# design.net
KiCad netlist of a schematic drawn in EasyEDA Pro
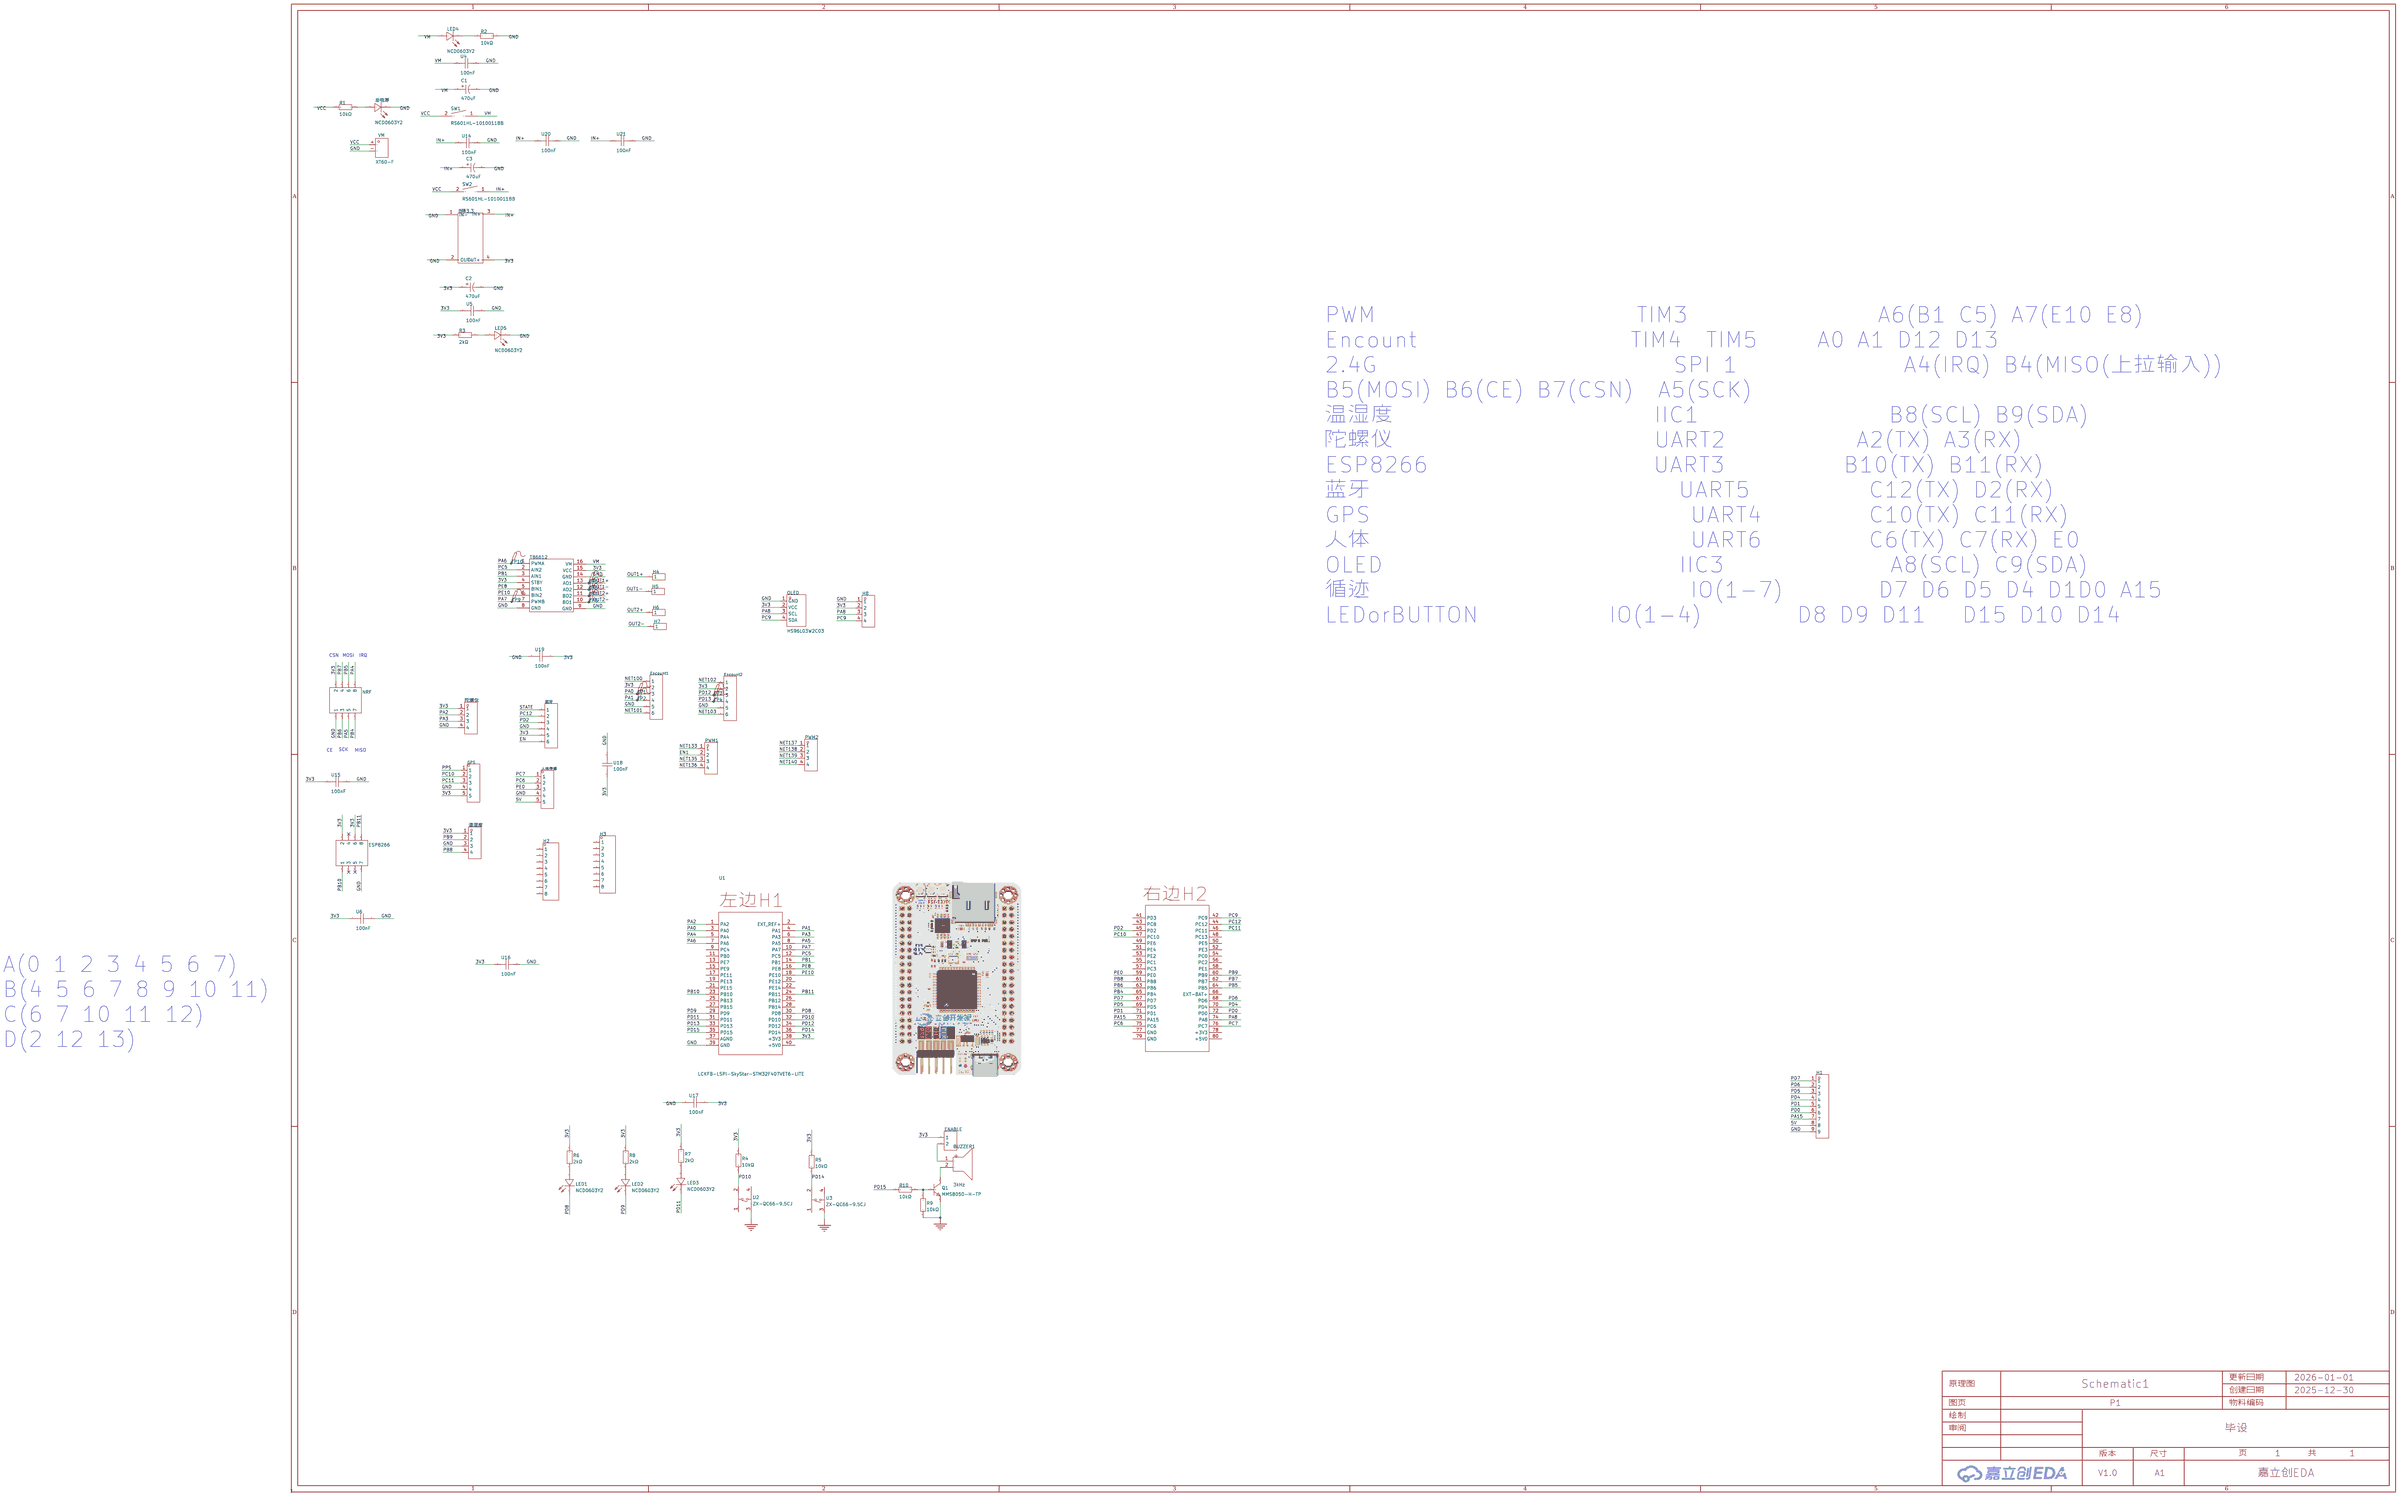
[diagram p0: schematic sheet]

(export (version "E")
  (design (tool "Eeschema 10.0.6"))
  (components
    (comp (ref "8降3.3")
      (value "~")
      (footprint "easyedapro:DCDC")
      (libsource (lib "easyedapro") (part "DCDC"))
    )
    (comp (ref "BUZZER1")
      (value "3kHz")
      (footprint "easyedapro:BUZ-TH_BD9.0-P5.00-D0.6-FD")
      (description "驱动方式:有源(内含驱动线路);构造类型:电磁式;频率:3kHz;声压(SPL):85dB;")
      (fields (field (name "Manufacturer Part") "HNB09A03") (field (name "Manufacturer") "华能"))
      (libsource (lib "easyedapro") (part "HNB09A03"))
    )
    (comp (ref "C1")
      (value "470uF")
      (footprint "easyedapro:CAP-TH_BD8.0-P3.50-D0.6-FD_1")
      (description "容值:470uF;精度:±20%;额定电压:25V;纹波电流:905mA@100kHz;等效串联电阻(ESR):69mΩ@100kHz;")
      (fields
        (field (name "Manufacturer Part") "CD2884771EM0812VFL")
        (field (name "Manufacturer") "HRK(鸿瑞凯电子)")
      )
      (libsource (lib "easyedapro") (part "CD2884771EM0812VFL"))
    )
    (comp (ref "C2")
      (value "470uF")
      (footprint "easyedapro:CAP-TH_BD8.0-P3.50-D0.6-FD_1")
      (description "容值:470uF;精度:±20%;额定电压:25V;纹波电流:905mA@100kHz;等效串联电阻(ESR):69mΩ@100kHz;")
      (fields
        (field (name "Manufacturer Part") "CD2884771EM0812VFL")
        (field (name "Manufacturer") "HRK(鸿瑞凯电子)")
      )
      (libsource (lib "easyedapro") (part "CD2884771EM0812VFL"))
    )
    (comp (ref "C3")
      (value "470uF")
      (footprint "easyedapro:CAP-TH_BD8.0-P3.50-D0.6-FD_1")
      (description "容值:470uF;精度:±20%;额定电压:25V;纹波电流:905mA@100kHz;等效串联电阻(ESR):69mΩ@100kHz;")
      (fields
        (field (name "Manufacturer Part") "CD2884771EM0812VFL")
        (field (name "Manufacturer") "HRK(鸿瑞凯电子)")
      )
      (libsource (lib "easyedapro") (part "CD2884771EM0812VFL"))
    )
    (comp (ref "ENABLE")
      (value "~")
      (footprint "easyedapro:HDR-TH_2P-P2.54-V-F")
      (libsource (lib "easyedapro") (part "Header-Female-2.54_1x2"))
    )
    (comp (ref "Encount1")
      (value "~")
      (footprint "easyedapro:HDR-TH_6P-P2.54-V-M-1")
      (libsource (lib "easyedapro") (part "Header-Male-2.54_1x6"))
    )
    (comp (ref "Encount2")
      (value "~")
      (footprint "easyedapro:HDR-TH_6P-P2.54-V-M-1")
      (libsource (lib "easyedapro") (part "Header-Male-2.54_1x6"))
    )
    (comp (ref "ESP8266")
      (value "~")
      (footprint "easyedapro:HDR-TH_8P-P2.54-V-F-R2-C4-S2.54-1")
      (libsource (lib "easyedapro") (part "HDR-F-2.54_2x4"))
    )
    (comp (ref "GPS")
      (value "~")
      (footprint "easyedapro:HDR-TH_5P-P2.54-V-M")
      (libsource (lib "easyedapro") (part "MTP125-1105S1"))
    )
    (comp (ref "H1")
      (value "~")
      (footprint "easyedapro:HDR-TH_9P-P2.54-V-M")
      (libsource (lib "easyedapro") (part "PZ254V-11-09P"))
    )
    (comp (ref "H2")
      (value "~")
      (footprint "easyedapro:HDR-TH_8P-P2.54-V-M")
      (libsource (lib "easyedapro") (part "Header-Male-2.54_1x8"))
    )
    (comp (ref "H3")
      (value "~")
      (footprint "easyedapro:HDR-TH_8P-P2.54-V-M")
      (libsource (lib "easyedapro") (part "Header-Male-2.54_1x8"))
    )
    (comp (ref "H4")
      (value "~")
      (footprint "easyedapro:HDR-TH_1P-V-M_XKB_X4611WV-01I-C28D40")
      (libsource (lib "easyedapro") (part "HDR_1x1"))
    )
    (comp (ref "H5")
      (value "~")
      (footprint "easyedapro:HDR-TH_1P-V-M_XKB_X4611WV-01I-C28D40")
      (libsource (lib "easyedapro") (part "HDR_1x1"))
    )
    (comp (ref "H6")
      (value "~")
      (footprint "easyedapro:HDR-TH_1P-V-M_XKB_X4611WV-01I-C28D40")
      (libsource (lib "easyedapro") (part "HDR_1x1"))
    )
    (comp (ref "H7")
      (value "~")
      (footprint "easyedapro:HDR-TH_1P-V-M_XKB_X4611WV-01I-C28D40")
      (libsource (lib "easyedapro") (part "HDR_1x1"))
    )
    (comp (ref "H8")
      (value "~")
      (footprint "easyedapro:HDR-TH_4P-P2.54-V-M")
      (libsource (lib "easyedapro") (part "PZ254V-11-04P"))
    )
    (comp (ref "LED1")
      (value "NCD0603Y2")
      (footprint "easyedapro:LED0603-RD")
      (fields (field (name "Manufacturer") "国星光电"))
      (libsource (lib "easyedapro") (part "FC-1608YXK-585F08"))
    )
    (comp (ref "LED2")
      (value "NCD0603Y2")
      (footprint "easyedapro:LED0603-RD")
      (fields (field (name "Manufacturer") "国星光电"))
      (libsource (lib "easyedapro") (part "FC-1608YXK-585F08"))
    )
    (comp (ref "LED3")
      (value "NCD0603Y2")
      (footprint "easyedapro:LED0603-RD")
      (fields (field (name "Manufacturer") "国星光电"))
      (libsource (lib "easyedapro") (part "FC-1608YXK-585F08"))
    )
    (comp (ref "LED4")
      (value "NCD0603Y2")
      (footprint "easyedapro:LED0603-RD")
      (fields (field (name "Manufacturer") "国星光电"))
      (libsource (lib "easyedapro") (part "FC-1608YXK-585F08"))
    )
    (comp (ref "LED5")
      (value "NCD0603Y2")
      (footprint "easyedapro:LED0603-RD")
      (fields (field (name "Manufacturer") "国星光电"))
      (libsource (lib "easyedapro") (part "FC-1608YXK-585F08"))
    )
    (comp (ref "NRF")
      (value "~")
      (footprint "easyedapro:HDR-TH_8P-P2.54-V-F-R2-C4-S2.54-1")
      (libsource (lib "easyedapro") (part "HDR-F-2.54_2x4"))
    )
    (comp (ref "OLED")
      (value "HS96L03W2C03")
      (footprint "easyedapro:OLED-TH_L27.8-W27.2-P2.54_C9900033791")
      (description "主控芯片:SSD1315;接口类型:I2C;尺寸(inch):0.96;像素分辨率:128x64;")
      (fields (field (name "Manufacturer") "HS(汉昇)"))
      (libsource (lib "easyedapro") (part "HS96L03W2C03"))
    )
    (comp (ref "PWM1")
      (value "~")
      (footprint "easyedapro:HDR-TH_4P-P2.54-V-M")
      (libsource (lib "easyedapro") (part "PZ254V-11-04P"))
    )
    (comp (ref "PWM2")
      (value "~")
      (footprint "easyedapro:HDR-TH_4P-P2.54-V-M")
      (libsource (lib "easyedapro") (part "PZ254V-11-04P"))
    )
    (comp (ref "Q1")
      (value "MMS8050-H-TP")
      (footprint "easyedapro:SOT-23-3_L2.9-W1.3-P1.90-LS2.4-BR")
      (description "晶体管类型:NPN;集电极电流(Ic):500mA;集射极击穿电压(Vceo):25V;耗散功率(Pd):300mW;直流电流增益(hFE):120@50mA,1V;")
      (fields (field (name "Manufacturer") "MCC(美微科)"))
      (libsource (lib "easyedapro") (part "MMS8050-H-TP"))
    )
    (comp (ref "R1")
      (value "10kΩ")
      (footprint "easyedapro:R0603")
      (description "电阻类型:厚膜电阻;阻值:4.7kΩ;精度:±1%;功率:100mW;工作电压:75V;温度系数:±100ppm/°C;")
      (fields
        (field (name "Manufacturer Part") "0603WAF4701T5E")
        (field (name "Manufacturer") "UNI-ROYAL(厚声)")
      )
      (libsource (lib "easyedapro") (part "0603WAF4701T5E"))
    )
    (comp (ref "R2")
      (value "10kΩ")
      (footprint "easyedapro:R0603")
      (description "电阻类型:厚膜电阻;阻值:4.7kΩ;精度:±1%;功率:100mW;工作电压:75V;温度系数:±100ppm/°C;")
      (fields
        (field (name "Manufacturer Part") "0603WAF4701T5E")
        (field (name "Manufacturer") "UNI-ROYAL(厚声)")
      )
      (libsource (lib "easyedapro") (part "0603WAF4701T5E"))
    )
    (comp (ref "R3")
      (value "2kΩ")
      (footprint "easyedapro:R0603")
      (description "电阻类型:厚膜电阻;阻值:4.7kΩ;精度:±1%;功率:100mW;工作电压:75V;温度系数:±100ppm/°C;")
      (fields
        (field (name "Manufacturer Part") "0603WAF4701T5E")
        (field (name "Manufacturer") "UNI-ROYAL(厚声)")
      )
      (libsource (lib "easyedapro") (part "0603WAF4701T5E"))
    )
    (comp (ref "R4")
      (value "10kΩ")
      (footprint "easyedapro:R0603")
      (description "电阻类型:厚膜电阻;阻值:4.7kΩ;精度:±1%;功率:100mW;工作电压:75V;温度系数:±100ppm/°C;")
      (fields
        (field (name "Manufacturer Part") "0603WAF4701T5E")
        (field (name "Manufacturer") "UNI-ROYAL(厚声)")
      )
      (libsource (lib "easyedapro") (part "0603WAF4701T5E"))
    )
    (comp (ref "R5")
      (value "10kΩ")
      (footprint "easyedapro:R0603")
      (description "电阻类型:厚膜电阻;阻值:4.7kΩ;精度:±1%;功率:100mW;工作电压:75V;温度系数:±100ppm/°C;")
      (fields
        (field (name "Manufacturer Part") "0603WAF4701T5E")
        (field (name "Manufacturer") "UNI-ROYAL(厚声)")
      )
      (libsource (lib "easyedapro") (part "0603WAF4701T5E"))
    )
    (comp (ref "R6")
      (value "2kΩ")
      (footprint "easyedapro:R0603")
      (description "电阻类型:厚膜电阻;阻值:4.7kΩ;精度:±1%;功率:100mW;工作电压:75V;温度系数:±100ppm/°C;")
      (fields
        (field (name "Manufacturer Part") "0603WAF4701T5E")
        (field (name "Manufacturer") "UNI-ROYAL(厚声)")
      )
      (libsource (lib "easyedapro") (part "0603WAF4701T5E"))
    )
    (comp (ref "R7")
      (value "2kΩ")
      (footprint "easyedapro:R0603")
      (description "电阻类型:厚膜电阻;阻值:4.7kΩ;精度:±1%;功率:100mW;工作电压:75V;温度系数:±100ppm/°C;")
      (fields
        (field (name "Manufacturer Part") "0603WAF4701T5E")
        (field (name "Manufacturer") "UNI-ROYAL(厚声)")
      )
      (libsource (lib "easyedapro") (part "0603WAF4701T5E"))
    )
    (comp (ref "R8")
      (value "2kΩ")
      (footprint "easyedapro:R0603")
      (description "电阻类型:厚膜电阻;阻值:4.7kΩ;精度:±1%;功率:100mW;工作电压:75V;温度系数:±100ppm/°C;")
      (fields
        (field (name "Manufacturer Part") "0603WAF4701T5E")
        (field (name "Manufacturer") "UNI-ROYAL(厚声)")
      )
      (libsource (lib "easyedapro") (part "0603WAF4701T5E"))
    )
    (comp (ref "R9")
      (value "10kΩ")
      (footprint "easyedapro:R0603")
      (description "电阻类型:厚膜电阻;阻值:4.7kΩ;精度:±1%;功率:100mW;工作电压:75V;温度系数:±100ppm/°C;")
      (fields
        (field (name "Manufacturer Part") "0603WAF4701T5E")
        (field (name "Manufacturer") "UNI-ROYAL(厚声)")
      )
      (libsource (lib "easyedapro") (part "0603WAF4701T5E"))
    )
    (comp (ref "R10")
      (value "10kΩ")
      (footprint "easyedapro:R0603")
      (description "电阻类型:厚膜电阻;阻值:4.7kΩ;精度:±1%;功率:100mW;工作电压:75V;温度系数:±100ppm/°C;")
      (fields
        (field (name "Manufacturer Part") "0603WAF4701T5E")
        (field (name "Manufacturer") "UNI-ROYAL(厚声)")
      )
      (libsource (lib "easyedapro") (part "0603WAF4701T5E"))
    )
    (comp (ref "SW1")
      (value "RS601HL-1010011BB")
      (footprint "easyedapro:SW-TH_RS601HL-1010011BB")
      (description "带灯:无;引脚样式:焊片;额定电流:3A;额定电压(AC):250V;额定电压(DC):-;电路结构:单刀单掷;机械寿命:1万次;")
      (fields (field (name "Manufacturer") "HCTL(华灿天禄)"))
      (libsource (lib "easyedapro") (part "RS601HL-1010011BB"))
    )
    (comp (ref "SW2")
      (value "RS601HL-1010011BB")
      (footprint "easyedapro:SW-TH_RS601HL-1010011BB")
      (description "带灯:无;引脚样式:焊片;额定电流:3A;额定电压(AC):250V;额定电压(DC):-;电路结构:单刀单掷;机械寿命:1万次;")
      (fields (field (name "Manufacturer") "HCTL(华灿天禄)"))
      (libsource (lib "easyedapro") (part "RS601HL-1010011BB"))
    )
    (comp (ref "TB6612")
      (value "~")
      (footprint "easyedapro:TB6612模块")
      (libsource (lib "easyedapro") (part "TB6612模块"))
    )
    (comp (ref "TP1")
      (value "~")
      (footprint "easyedapro:Test-Point-0.5mm")
      (description "Test Point 测试点")
      (libsource (lib "easyedapro") (part "Test-Point"))
    )
    (comp (ref "TP2")
      (value "~")
      (footprint "easyedapro:Test-Point-0.5mm")
      (description "Test Point 测试点")
      (libsource (lib "easyedapro") (part "Test-Point"))
    )
    (comp (ref "TP3")
      (value "~")
      (footprint "easyedapro:Test-Point-0.5mm")
      (description "Test Point 测试点")
      (libsource (lib "easyedapro") (part "Test-Point"))
    )
    (comp (ref "TP4")
      (value "~")
      (footprint "easyedapro:Test-Point-0.5mm")
      (description "Test Point 测试点")
      (libsource (lib "easyedapro") (part "Test-Point"))
    )
    (comp (ref "TP5")
      (value "~")
      (footprint "easyedapro:Test-Point-0.5mm")
      (description "Test Point 测试点")
      (libsource (lib "easyedapro") (part "Test-Point"))
    )
    (comp (ref "TP6")
      (value "~")
      (footprint "easyedapro:Test-Point-0.5mm")
      (description "Test Point 测试点")
      (libsource (lib "easyedapro") (part "Test-Point"))
    )
    (comp (ref "TP7")
      (value "~")
      (footprint "easyedapro:Test-Point-0.5mm")
      (description "Test Point 测试点")
      (libsource (lib "easyedapro") (part "Test-Point"))
    )
    (comp (ref "TP8")
      (value "~")
      (footprint "easyedapro:Test-Point-0.5mm")
      (description "Test Point 测试点")
      (libsource (lib "easyedapro") (part "Test-Point"))
    )
    (comp (ref "TP9")
      (value "~")
      (footprint "easyedapro:Test-Point-0.5mm")
      (description "Test Point 测试点")
      (libsource (lib "easyedapro") (part "Test-Point"))
    )
    (comp (ref "TP10")
      (value "~")
      (footprint "easyedapro:Test-Point-0.5mm")
      (description "Test Point 测试点")
      (libsource (lib "easyedapro") (part "Test-Point"))
    )
    (comp (ref "U1")
      (value "LCKFB-LSPI-SkyStar-STM32F407VET6-LITE")
      (footprint "easyedapro:COMM-TH_LCKFB-LSPI-SKYSTAR-STM32F407VET6-LITE")
      (description "单板,不送排针")
      (fields (field (name "Manufacturer") "立创开发板"))
      (libsource (lib "easyedapro") (part "LCKFB-LSPI-SKYSTAR-STM32F407VET6-LITE"))
    )
    (comp (ref "U2")
      (value "ZX-QC66-9.5CJ")
      (footprint "easyedapro:SW-TH_4P-L6.0-W6.0-P4.50-LS6.3")
      (fields (field (name "Manufacturer") "Megastar(兆星)"))
      (libsource (lib "easyedapro") (part "ZX-QC66-9.5CJ"))
    )
    (comp (ref "U3")
      (value "ZX-QC66-9.5CJ")
      (footprint "easyedapro:SW-TH_4P-L6.0-W6.0-P4.50-LS6.3")
      (fields (field (name "Manufacturer") "Megastar(兆星)"))
      (libsource (lib "easyedapro") (part "ZX-QC66-9.5CJ"))
    )
    (comp (ref "U4")
      (value "100nF")
      (footprint "easyedapro:C0603")
      (description "容值:47pF;精度:±1%;额定电压:50V;温度系数:C0G;")
      (fields
        (field (name "Manufacturer Part") "VJ0603A470FXACW1BC")
        (field (name "Manufacturer") "VISHAY(威世)")
      )
      (libsource (lib "easyedapro") (part "VJ0603A470FXACW1BC"))
    )
    (comp (ref "U5")
      (value "100nF")
      (footprint "easyedapro:C0603")
      (description "容值:47pF;精度:±1%;额定电压:50V;温度系数:C0G;")
      (fields
        (field (name "Manufacturer Part") "VJ0603A470FXACW1BC")
        (field (name "Manufacturer") "VISHAY(威世)")
      )
      (libsource (lib "easyedapro") (part "VJ0603A470FXACW1BC"))
    )
    (comp (ref "U6")
      (value "100nF")
      (footprint "easyedapro:C0603")
      (description "容值:47pF;精度:±1%;额定电压:50V;温度系数:C0G;")
      (fields
        (field (name "Manufacturer Part") "VJ0603A470FXACW1BC")
        (field (name "Manufacturer") "VISHAY(威世)")
      )
      (libsource (lib "easyedapro") (part "VJ0603A470FXACW1BC"))
    )
    (comp (ref "U14")
      (value "100nF")
      (footprint "easyedapro:C0603")
      (description "容值:47pF;精度:±1%;额定电压:50V;温度系数:C0G;")
      (fields
        (field (name "Manufacturer Part") "VJ0603A470FXACW1BC")
        (field (name "Manufacturer") "VISHAY(威世)")
      )
      (libsource (lib "easyedapro") (part "VJ0603A470FXACW1BC"))
    )
    (comp (ref "U15")
      (value "100nF")
      (footprint "easyedapro:C0603")
      (description "容值:47pF;精度:±1%;额定电压:50V;温度系数:C0G;")
      (fields
        (field (name "Manufacturer Part") "VJ0603A470FXACW1BC")
        (field (name "Manufacturer") "VISHAY(威世)")
      )
      (libsource (lib "easyedapro") (part "VJ0603A470FXACW1BC"))
    )
    (comp (ref "U16")
      (value "100nF")
      (footprint "easyedapro:C0603")
      (description "容值:47pF;精度:±1%;额定电压:50V;温度系数:C0G;")
      (fields
        (field (name "Manufacturer Part") "VJ0603A470FXACW1BC")
        (field (name "Manufacturer") "VISHAY(威世)")
      )
      (libsource (lib "easyedapro") (part "VJ0603A470FXACW1BC"))
    )
    (comp (ref "U17")
      (value "100nF")
      (footprint "easyedapro:C0603")
      (description "容值:47pF;精度:±1%;额定电压:50V;温度系数:C0G;")
      (fields
        (field (name "Manufacturer Part") "VJ0603A470FXACW1BC")
        (field (name "Manufacturer") "VISHAY(威世)")
      )
      (libsource (lib "easyedapro") (part "VJ0603A470FXACW1BC"))
    )
    (comp (ref "U18")
      (value "100nF")
      (footprint "easyedapro:C0603")
      (description "容值:47pF;精度:±1%;额定电压:50V;温度系数:C0G;")
      (fields
        (field (name "Manufacturer Part") "VJ0603A470FXACW1BC")
        (field (name "Manufacturer") "VISHAY(威世)")
      )
      (libsource (lib "easyedapro") (part "VJ0603A470FXACW1BC"))
    )
    (comp (ref "U19")
      (value "100nF")
      (footprint "easyedapro:C0603")
      (description "容值:47pF;精度:±1%;额定电压:50V;温度系数:C0G;")
      (fields
        (field (name "Manufacturer Part") "VJ0603A470FXACW1BC")
        (field (name "Manufacturer") "VISHAY(威世)")
      )
      (libsource (lib "easyedapro") (part "VJ0603A470FXACW1BC"))
    )
    (comp (ref "U20")
      (value "100nF")
      (footprint "easyedapro:C0603")
      (description "容值:47pF;精度:±1%;额定电压:50V;温度系数:C0G;")
      (fields
        (field (name "Manufacturer Part") "VJ0603A470FXACW1BC")
        (field (name "Manufacturer") "VISHAY(威世)")
      )
      (libsource (lib "easyedapro") (part "VJ0603A470FXACW1BC"))
    )
    (comp (ref "U21")
      (value "100nF")
      (footprint "easyedapro:C0603")
      (description "容值:47pF;精度:±1%;额定电压:50V;温度系数:C0G;")
      (fields
        (field (name "Manufacturer Part") "VJ0603A470FXACW1BC")
        (field (name "Manufacturer") "VISHAY(威世)")
      )
      (libsource (lib "easyedapro") (part "VJ0603A470FXACW1BC"))
    )
    (comp (ref "VM")
      (value "XT60-F")
      (footprint "easyedapro:CONN-TH_XT60PB-F")
      (description "类别:-;类型1:-;")
      (fields (field (name "Manufacturer") "AMASS(艾迈斯)"))
      (libsource (lib "easyedapro") (part "XT60-F"))
    )
    (comp (ref "人体传感")
      (value "~")
      (footprint "easyedapro:HDR-TH_5P-P2.54-V-M")
      (libsource (lib "easyedapro") (part "MTP125-1105S1"))
    )
    (comp (ref "总电源")
      (value "NCD0603Y2")
      (footprint "easyedapro:LED0603-RD")
      (fields (field (name "Manufacturer") "国星光电"))
      (libsource (lib "easyedapro") (part "FC-1608YXK-585F08"))
    )
    (comp (ref "温湿度")
      (value "~")
      (footprint "easyedapro:HDR-TH_4P-P2.54-V-M")
      (libsource (lib "easyedapro") (part "PZ254V-11-04P"))
    )
    (comp (ref "蓝牙")
      (value "~")
      (footprint "easyedapro:HDR-TH_6P-P2.54-V-M-1")
      (libsource (lib "easyedapro") (part "Header-Male-2.54_1x6"))
    )
    (comp (ref "陀螺仪")
      (value "~")
      (footprint "easyedapro:HDR-TH_4P-P2.54-V-M")
      (libsource (lib "easyedapro") (part "PZ254V-11-04P"))
    )
  )
  (nets
    (net (code "1") (name "/3V3") (class "Default")
      (node (ref "8降3.3") (pin "4") (pinfunction "OUT+_4") (pintype "input"))
      (node (ref "C2") (pin "1") (pinfunction "1_1") (pintype "input"))
      (node (ref "ENABLE") (pin "1") (pinfunction "1_1") (pintype "input"))
      (node (ref "ESP8266") (pin "2") (pinfunction "2_2") (pintype "input"))
      (node (ref "ESP8266") (pin "6") (pinfunction "6_6") (pintype "input"))
      (node (ref "Encount1") (pin "2") (pinfunction "2_2") (pintype "input"))
      (node (ref "Encount2") (pin "2") (pinfunction "2_2") (pintype "input"))
      (node (ref "GPS") (pin "5") (pinfunction "5_5") (pintype "input"))
      (node (ref "H8") (pin "2") (pinfunction "2_2") (pintype "unspecified"))
      (node (ref "NRF") (pin "2") (pinfunction "2_2") (pintype "input"))
      (node (ref "OLED") (pin "2") (pinfunction "VCC_2") (pintype "unspecified"))
      (node (ref "R3") (pin "2") (pinfunction "2_2") (pintype "input"))
      (node (ref "R4") (pin "2") (pinfunction "2_2") (pintype "input"))
      (node (ref "R5") (pin "2") (pinfunction "2_2") (pintype "input"))
      (node (ref "R6") (pin "2") (pinfunction "2_2") (pintype "input"))
      (node (ref "R7") (pin "2") (pinfunction "2_2") (pintype "input"))
      (node (ref "R8") (pin "2") (pinfunction "2_2") (pintype "input"))
      (node (ref "TB6612") (pin "15") (pinfunction "VCC_15") (pintype "input"))
      (node (ref "TB6612") (pin "4") (pinfunction "STBY_4") (pintype "input"))
      (node (ref "U1") (pin "38") (pinfunction "+3V3_38") (pintype "unspecified"))
      (node (ref "U15") (pin "1") (pinfunction "1_1") (pintype "unspecified"))
      (node (ref "U16") (pin "1") (pinfunction "1_1") (pintype "unspecified"))
      (node (ref "U17") (pin "1") (pinfunction "1_1") (pintype "unspecified"))
      (node (ref "U18") (pin "1") (pinfunction "1_1") (pintype "unspecified"))
      (node (ref "U19") (pin "1") (pinfunction "1_1") (pintype "unspecified"))
      (node (ref "U5") (pin "1") (pinfunction "1_1") (pintype "unspecified"))
      (node (ref "U6") (pin "1") (pinfunction "1_1") (pintype "unspecified"))
      (node (ref "温湿度") (pin "1") (pinfunction "1_1") (pintype "unspecified"))
      (node (ref "蓝牙") (pin "5") (pinfunction "5_5") (pintype "input"))
      (node (ref "陀螺仪") (pin "1") (pinfunction "1_1") (pintype "unspecified"))
    )
    (net (code "2") (name "/5V") (class "Default")
      (node (ref "H1") (pin "8") (pinfunction "8_8") (pintype "unspecified"))
      (node (ref "人体传感") (pin "5") (pinfunction "5_5") (pintype "input"))
    )
    (net (code "3") (name "/EN") (class "Default")
      (node (ref "蓝牙") (pin "6") (pinfunction "6_6") (pintype "input"))
    )
    (net (code "4") (name "/EN1") (class "Default")
      (node (ref "PWM1") (pin "2") (pinfunction "2_2") (pintype "unspecified"))
    )
    (net (code "5") (name "/IN+") (class "Default")
      (node (ref "8降3.3") (pin "3") (pinfunction "IN+_3") (pintype "input"))
      (node (ref "C3") (pin "1") (pinfunction "1_1") (pintype "input"))
      (node (ref "SW2") (pin "1") (pinfunction "1_1") (pintype "input"))
      (node (ref "U14") (pin "1") (pinfunction "1_1") (pintype "unspecified"))
      (node (ref "U20") (pin "1") (pinfunction "1_1") (pintype "unspecified"))
      (node (ref "U21") (pin "1") (pinfunction "1_1") (pintype "unspecified"))
    )
    (net (code "6") (name "/NET100") (class "Default")
      (node (ref "Encount1") (pin "1") (pinfunction "1_1") (pintype "input"))
    )
    (net (code "7") (name "/NET101") (class "Default")
      (node (ref "Encount1") (pin "6") (pinfunction "6_6") (pintype "input"))
    )
    (net (code "8") (name "/NET102") (class "Default")
      (node (ref "Encount2") (pin "1") (pinfunction "1_1") (pintype "input"))
    )
    (net (code "9") (name "/NET103") (class "Default")
      (node (ref "Encount2") (pin "6") (pinfunction "6_6") (pintype "input"))
    )
    (net (code "10") (name "/NET133") (class "Default")
      (node (ref "PWM1") (pin "1") (pinfunction "1_1") (pintype "unspecified"))
    )
    (net (code "11") (name "/NET135") (class "Default")
      (node (ref "PWM1") (pin "3") (pinfunction "3_3") (pintype "unspecified"))
    )
    (net (code "12") (name "/NET136") (class "Default")
      (node (ref "PWM1") (pin "4") (pinfunction "4_4") (pintype "unspecified"))
    )
    (net (code "13") (name "/NET137") (class "Default")
      (node (ref "PWM2") (pin "1") (pinfunction "1_1") (pintype "unspecified"))
    )
    (net (code "14") (name "/NET138") (class "Default")
      (node (ref "PWM2") (pin "2") (pinfunction "2_2") (pintype "unspecified"))
    )
    (net (code "15") (name "/NET139") (class "Default")
      (node (ref "PWM2") (pin "3") (pinfunction "3_3") (pintype "unspecified"))
    )
    (net (code "16") (name "/NET140") (class "Default")
      (node (ref "PWM2") (pin "4") (pinfunction "4_4") (pintype "unspecified"))
    )
    (net (code "17") (name "/OUT1+") (class "Default")
      (node (ref "H4") (pin "1") (pinfunction "1_1") (pintype "unspecified"))
      (node (ref "TB6612") (pin "13") (pinfunction "AO1_13") (pintype "input"))
      (node (ref "TP5") (pin "1") (pinfunction "1_1") (pintype "input"))
    )
    (net (code "18") (name "/OUT1-") (class "Default")
      (node (ref "H5") (pin "1") (pinfunction "1_1") (pintype "unspecified"))
      (node (ref "TB6612") (pin "12") (pinfunction "AO2_12") (pintype "input"))
      (node (ref "TP6") (pin "1") (pinfunction "1_1") (pintype "input"))
    )
    (net (code "19") (name "/OUT2+") (class "Default")
      (node (ref "H6") (pin "1") (pinfunction "1_1") (pintype "unspecified"))
      (node (ref "TB6612") (pin "11") (pinfunction "BO2_11") (pintype "input"))
      (node (ref "TP7") (pin "1") (pinfunction "1_1") (pintype "input"))
    )
    (net (code "20") (name "/OUT2-") (class "Default")
      (node (ref "H7") (pin "1") (pinfunction "1_1") (pintype "unspecified"))
      (node (ref "TB6612") (pin "10") (pinfunction "BO1_10") (pintype "input"))
      (node (ref "TP8") (pin "1") (pinfunction "1_1") (pintype "input"))
    )
    (net (code "21") (name "/PA0") (class "Default")
      (node (ref "Encount1") (pin "3") (pinfunction "3_3") (pintype "input"))
      (node (ref "TP1") (pin "1") (pinfunction "1_1") (pintype "input"))
      (node (ref "U1") (pin "3") (pinfunction "PA0_3") (pintype "bidirectional"))
    )
    (net (code "22") (name "/PA1") (class "Default")
      (node (ref "Encount1") (pin "4") (pinfunction "4_4") (pintype "input"))
      (node (ref "TP2") (pin "1") (pinfunction "1_1") (pintype "input"))
      (node (ref "U1") (pin "4") (pinfunction "PA1_4") (pintype "unspecified"))
    )
    (net (code "23") (name "/PA2") (class "Default")
      (node (ref "U1") (pin "1") (pinfunction "PA2_1") (pintype "unspecified"))
      (node (ref "陀螺仪") (pin "2") (pinfunction "2_2") (pintype "unspecified"))
    )
    (net (code "24") (name "/PA3") (class "Default")
      (node (ref "U1") (pin "6") (pinfunction "PA3_6") (pintype "unspecified"))
      (node (ref "陀螺仪") (pin "3") (pinfunction "3_3") (pintype "unspecified"))
    )
    (net (code "25") (name "/PA4") (class "Default")
      (node (ref "NRF") (pin "8") (pinfunction "8_8") (pintype "input"))
      (node (ref "U1") (pin "5") (pinfunction "PA4_5") (pintype "unspecified"))
    )
    (net (code "26") (name "/PA5") (class "Default")
      (node (ref "NRF") (pin "5") (pinfunction "5_5") (pintype "input"))
      (node (ref "U1") (pin "8") (pinfunction "PA5_8") (pintype "unspecified"))
    )
    (net (code "27") (name "/PA6") (class "Default")
      (node (ref "TB6612") (pin "1") (pinfunction "PWMA_1") (pintype "input"))
      (node (ref "TP10") (pin "1") (pinfunction "1_1") (pintype "input"))
      (node (ref "U1") (pin "7") (pinfunction "PA6_7") (pintype "unspecified"))
    )
    (net (code "28") (name "/PA7") (class "Default")
      (node (ref "TB6612") (pin "7") (pinfunction "PWMB_7") (pintype "input"))
      (node (ref "TP9") (pin "1") (pinfunction "1_1") (pintype "input"))
      (node (ref "U1") (pin "10") (pinfunction "PA7_10") (pintype "unspecified"))
    )
    (net (code "29") (name "/PA8") (class "Default")
      (node (ref "H8") (pin "3") (pinfunction "3_3") (pintype "unspecified"))
      (node (ref "OLED") (pin "3") (pinfunction "SCL_3") (pintype "unspecified"))
      (node (ref "U1") (pin "74") (pinfunction "PA8_74") (pintype "unspecified"))
    )
    (net (code "30") (name "/PA15") (class "Default")
      (node (ref "H1") (pin "7") (pinfunction "7_7") (pintype "unspecified"))
      (node (ref "U1") (pin "73") (pinfunction "PA15_73") (pintype "unspecified"))
    )
    (net (code "31") (name "/PB1") (class "Default")
      (node (ref "TB6612") (pin "3") (pinfunction "AIN1_3") (pintype "input"))
      (node (ref "U1") (pin "14") (pinfunction "PB1_14") (pintype "unspecified"))
    )
    (net (code "32") (name "/PB4") (class "Default")
      (node (ref "NRF") (pin "7") (pinfunction "7_7") (pintype "input"))
      (node (ref "U1") (pin "65") (pinfunction "PB4_65") (pintype "unspecified"))
    )
    (net (code "33") (name "/PB5") (class "Default")
      (node (ref "NRF") (pin "6") (pinfunction "6_6") (pintype "input"))
      (node (ref "U1") (pin "64") (pinfunction "PB5_64") (pintype "unspecified"))
    )
    (net (code "34") (name "/PB6") (class "Default")
      (node (ref "NRF") (pin "3") (pinfunction "3_3") (pintype "input"))
      (node (ref "U1") (pin "63") (pinfunction "PB6_63") (pintype "unspecified"))
    )
    (net (code "35") (name "/PB7") (class "Default")
      (node (ref "NRF") (pin "4") (pinfunction "4_4") (pintype "input"))
      (node (ref "U1") (pin "62") (pinfunction "PB7_62") (pintype "unspecified"))
    )
    (net (code "36") (name "/PB8") (class "Default")
      (node (ref "U1") (pin "61") (pinfunction "PB8_61") (pintype "unspecified"))
      (node (ref "温湿度") (pin "4") (pinfunction "4_4") (pintype "unspecified"))
    )
    (net (code "37") (name "/PB9") (class "Default")
      (node (ref "U1") (pin "60") (pinfunction "PB9_60") (pintype "unspecified"))
      (node (ref "温湿度") (pin "2") (pinfunction "2_2") (pintype "unspecified"))
    )
    (net (code "38") (name "/PB10") (class "Default")
      (node (ref "ESP8266") (pin "1") (pinfunction "1_1") (pintype "input"))
      (node (ref "U1") (pin "23") (pinfunction "PB10_23") (pintype "unspecified"))
    )
    (net (code "39") (name "/PB11") (class "Default")
      (node (ref "ESP8266") (pin "8") (pinfunction "8_8") (pintype "input"))
      (node (ref "U1") (pin "24") (pinfunction "PB11_24") (pintype "unspecified"))
    )
    (net (code "40") (name "/PC5") (class "Default")
      (node (ref "TB6612") (pin "2") (pinfunction "AIN2_2") (pintype "input"))
      (node (ref "U1") (pin "12") (pinfunction "PC5_12") (pintype "unspecified"))
    )
    (net (code "41") (name "/PC6") (class "Default")
      (node (ref "U1") (pin "75") (pinfunction "PC6_75") (pintype "unspecified"))
      (node (ref "人体传感") (pin "2") (pinfunction "2_2") (pintype "input"))
    )
    (net (code "42") (name "/PC7") (class "Default")
      (node (ref "U1") (pin "76") (pinfunction "PC7_76") (pintype "unspecified"))
      (node (ref "人体传感") (pin "1") (pinfunction "1_1") (pintype "input"))
    )
    (net (code "43") (name "/PC9") (class "Default")
      (node (ref "H8") (pin "4") (pinfunction "4_4") (pintype "unspecified"))
      (node (ref "OLED") (pin "4") (pinfunction "SDA_4") (pintype "unspecified"))
      (node (ref "U1") (pin "42") (pinfunction "PC9_42") (pintype "unspecified"))
    )
    (net (code "44") (name "/PC10") (class "Default")
      (node (ref "GPS") (pin "2") (pinfunction "2_2") (pintype "input"))
      (node (ref "U1") (pin "47") (pinfunction "PC10_47") (pintype "unspecified"))
    )
    (net (code "45") (name "/PC11") (class "Default")
      (node (ref "GPS") (pin "3") (pinfunction "3_3") (pintype "input"))
      (node (ref "U1") (pin "46") (pinfunction "PC11_46") (pintype "unspecified"))
    )
    (net (code "46") (name "/PC12") (class "Default")
      (node (ref "U1") (pin "44") (pinfunction "PC12_44") (pintype "unspecified"))
      (node (ref "蓝牙") (pin "2") (pinfunction "2_2") (pintype "input"))
    )
    (net (code "47") (name "/PD0") (class "Default")
      (node (ref "H1") (pin "6") (pinfunction "6_6") (pintype "unspecified"))
      (node (ref "U1") (pin "72") (pinfunction "PD0_72") (pintype "unspecified"))
    )
    (net (code "48") (name "/PD1") (class "Default")
      (node (ref "H1") (pin "5") (pinfunction "5_5") (pintype "unspecified"))
      (node (ref "U1") (pin "71") (pinfunction "PD1_71") (pintype "unspecified"))
    )
    (net (code "49") (name "/PD2") (class "Default")
      (node (ref "U1") (pin "45") (pinfunction "PD2_45") (pintype "unspecified"))
      (node (ref "蓝牙") (pin "3") (pinfunction "3_3") (pintype "input"))
    )
    (net (code "50") (name "/PD4") (class "Default")
      (node (ref "H1") (pin "4") (pinfunction "4_4") (pintype "unspecified"))
      (node (ref "U1") (pin "70") (pinfunction "PD4_70") (pintype "unspecified"))
    )
    (net (code "51") (name "/PD5") (class "Default")
      (node (ref "H1") (pin "3") (pinfunction "3_3") (pintype "unspecified"))
      (node (ref "U1") (pin "69") (pinfunction "PD5_69") (pintype "unspecified"))
    )
    (net (code "52") (name "/PD6") (class "Default")
      (node (ref "H1") (pin "2") (pinfunction "2_2") (pintype "unspecified"))
      (node (ref "U1") (pin "68") (pinfunction "PD6_68") (pintype "unspecified"))
    )
    (net (code "53") (name "/PD7") (class "Default")
      (node (ref "H1") (pin "1") (pinfunction "1_1") (pintype "unspecified"))
      (node (ref "U1") (pin "67") (pinfunction "PD7_67") (pintype "unspecified"))
    )
    (net (code "54") (name "/PD8") (class "Default")
      (node (ref "LED1") (pin "1") (pinfunction "K_1") (pintype "unspecified"))
      (node (ref "U1") (pin "30") (pinfunction "PD8_30") (pintype "unspecified"))
    )
    (net (code "55") (name "/PD9") (class "Default")
      (node (ref "LED2") (pin "1") (pinfunction "K_1") (pintype "unspecified"))
      (node (ref "U1") (pin "29") (pinfunction "PD9_29") (pintype "unspecified"))
    )
    (net (code "56") (name "/PD10") (class "Default")
      (node (ref "R4") (pin "1") (pinfunction "1_1") (pintype "input"))
      (node (ref "U1") (pin "32") (pinfunction "PD10_32") (pintype "unspecified"))
      (node (ref "U2") (pin "2") (pinfunction "2_2") (pintype "unspecified"))
    )
    (net (code "57") (name "/PD11") (class "Default")
      (node (ref "LED3") (pin "1") (pinfunction "K_1") (pintype "unspecified"))
      (node (ref "U1") (pin "31") (pinfunction "PD11_31") (pintype "unspecified"))
    )
    (net (code "58") (name "/PD12") (class "Default")
      (node (ref "Encount2") (pin "3") (pinfunction "3_3") (pintype "input"))
      (node (ref "TP3") (pin "1") (pinfunction "1_1") (pintype "input"))
      (node (ref "U1") (pin "34") (pinfunction "PD12_34") (pintype "unspecified"))
    )
    (net (code "59") (name "/PD13") (class "Default")
      (node (ref "Encount2") (pin "4") (pinfunction "4_4") (pintype "input"))
      (node (ref "TP4") (pin "1") (pinfunction "1_1") (pintype "input"))
      (node (ref "U1") (pin "33") (pinfunction "PD13_33") (pintype "unspecified"))
    )
    (net (code "60") (name "/PD14") (class "Default")
      (node (ref "R5") (pin "1") (pinfunction "1_1") (pintype "input"))
      (node (ref "U1") (pin "36") (pinfunction "PD14_36") (pintype "unspecified"))
      (node (ref "U3") (pin "2") (pinfunction "2_2") (pintype "unspecified"))
    )
    (net (code "61") (name "/PD15") (class "Default")
      (node (ref "R10") (pin "1") (pinfunction "1_1") (pintype "input"))
      (node (ref "U1") (pin "35") (pinfunction "PD15_35") (pintype "unspecified"))
    )
    (net (code "62") (name "/PE0") (class "Default")
      (node (ref "U1") (pin "59") (pinfunction "PE0_59") (pintype "unspecified"))
      (node (ref "人体传感") (pin "3") (pinfunction "3_3") (pintype "input"))
    )
    (net (code "63") (name "/PE8") (class "Default")
      (node (ref "TB6612") (pin "5") (pinfunction "BIN1_5") (pintype "input"))
      (node (ref "U1") (pin "16") (pinfunction "PE8_16") (pintype "unspecified"))
    )
    (net (code "64") (name "/PE10") (class "Default")
      (node (ref "TB6612") (pin "6") (pinfunction "BIN2_6") (pintype "input"))
      (node (ref "U1") (pin "18") (pinfunction "PE10_18") (pintype "unspecified"))
    )
    (net (code "65") (name "/PPS") (class "Default")
      (node (ref "GPS") (pin "1") (pinfunction "1_1") (pintype "input"))
    )
    (net (code "66") (name "/STATE") (class "Default")
      (node (ref "蓝牙") (pin "1") (pinfunction "1_1") (pintype "input"))
    )
    (net (code "67") (name "/VCC") (class "Default")
      (node (ref "R1") (pin "2") (pinfunction "2_2") (pintype "input"))
      (node (ref "SW1") (pin "2") (pinfunction "2_2") (pintype "input"))
      (node (ref "SW2") (pin "2") (pinfunction "2_2") (pintype "input"))
      (node (ref "VM") (pin "+") (pinfunction "1_+") (pintype "unspecified"))
    )
    (net (code "68") (name "/VM") (class "Default")
      (node (ref "C1") (pin "1") (pinfunction "1_1") (pintype "input"))
      (node (ref "LED4") (pin "2") (pinfunction "A_2") (pintype "unspecified"))
      (node (ref "SW1") (pin "1") (pinfunction "1_1") (pintype "input"))
      (node (ref "TB6612") (pin "16") (pinfunction "VM_16") (pintype "input"))
      (node (ref "U4") (pin "1") (pinfunction "1_1") (pintype "unspecified"))
    )
    (net (code "69") (name "GND") (class "Default")
      (node (ref "8降3.3") (pin "1") (pinfunction "IN-_1") (pintype "input"))
      (node (ref "8降3.3") (pin "2") (pinfunction "OUT-_2") (pintype "input"))
      (node (ref "C1") (pin "2") (pinfunction "2_2") (pintype "input"))
      (node (ref "C2") (pin "2") (pinfunction "2_2") (pintype "input"))
      (node (ref "C3") (pin "2") (pinfunction "2_2") (pintype "input"))
      (node (ref "ESP8266") (pin "7") (pinfunction "7_7") (pintype "input"))
      (node (ref "Encount1") (pin "5") (pinfunction "5_5") (pintype "input"))
      (node (ref "Encount2") (pin "5") (pinfunction "5_5") (pintype "input"))
      (node (ref "GPS") (pin "4") (pinfunction "4_4") (pintype "input"))
      (node (ref "H1") (pin "9") (pinfunction "9_9") (pintype "unspecified"))
      (node (ref "H8") (pin "1") (pinfunction "1_1") (pintype "unspecified"))
      (node (ref "LED5") (pin "1") (pinfunction "K_1") (pintype "unspecified"))
      (node (ref "NRF") (pin "1") (pinfunction "1_1") (pintype "input"))
      (node (ref "OLED") (pin "1") (pinfunction "GND_1") (pintype "unspecified"))
      (node (ref "Q1") (pin "2") (pinfunction "E_2") (pintype "input"))
      (node (ref "R2") (pin "1") (pinfunction "1_1") (pintype "input"))
      (node (ref "R9") (pin "2") (pinfunction "2_2") (pintype "input"))
      (node (ref "TB6612") (pin "14") (pinfunction "GND_14") (pintype "input"))
      (node (ref "TB6612") (pin "8") (pinfunction "GND_8") (pintype "input"))
      (node (ref "TB6612") (pin "9") (pinfunction "GND_9") (pintype "input"))
      (node (ref "U1") (pin "39") (pinfunction "GND_39") (pintype "unspecified"))
      (node (ref "U14") (pin "2") (pinfunction "2_2") (pintype "unspecified"))
      (node (ref "U15") (pin "2") (pinfunction "2_2") (pintype "unspecified"))
      (node (ref "U16") (pin "2") (pinfunction "2_2") (pintype "unspecified"))
      (node (ref "U17") (pin "2") (pinfunction "2_2") (pintype "unspecified"))
      (node (ref "U18") (pin "2") (pinfunction "2_2") (pintype "unspecified"))
      (node (ref "U19") (pin "2") (pinfunction "2_2") (pintype "unspecified"))
      (node (ref "U2") (pin "3") (pinfunction "3_3") (pintype "unspecified"))
      (node (ref "U20") (pin "2") (pinfunction "2_2") (pintype "unspecified"))
      (node (ref "U21") (pin "2") (pinfunction "2_2") (pintype "unspecified"))
      (node (ref "U3") (pin "3") (pinfunction "3_3") (pintype "unspecified"))
      (node (ref "U4") (pin "2") (pinfunction "2_2") (pintype "unspecified"))
      (node (ref "U5") (pin "2") (pinfunction "2_2") (pintype "unspecified"))
      (node (ref "U6") (pin "2") (pinfunction "2_2") (pintype "unspecified"))
      (node (ref "VM") (pin "-") (pinfunction "2_-") (pintype "unspecified"))
      (node (ref "人体传感") (pin "4") (pinfunction "4_4") (pintype "input"))
      (node (ref "总电源") (pin "1") (pinfunction "K_1") (pintype "unspecified"))
      (node (ref "温湿度") (pin "3") (pinfunction "3_3") (pintype "unspecified"))
      (node (ref "蓝牙") (pin "4") (pinfunction "4_4") (pintype "input"))
      (node (ref "陀螺仪") (pin "4") (pinfunction "4_4") (pintype "unspecified"))
    )
    (net (code "70") (name "Net-(BUZZER1-+)") (class "Default")
      (node (ref "BUZZER1") (pin "1") (pinfunction "+_1") (pintype "unspecified"))
      (node (ref "ENABLE") (pin "2") (pinfunction "2_2") (pintype "input"))
    )
    (net (code "71") (name "Net-(BUZZER1--)") (class "Default")
      (node (ref "BUZZER1") (pin "2") (pinfunction "-_2") (pintype "unspecified"))
      (node (ref "Q1") (pin "3") (pinfunction "C_3") (pintype "input"))
    )
    (net (code "72") (name "Net-(LED1-A)") (class "Default")
      (node (ref "LED1") (pin "2") (pinfunction "A_2") (pintype "unspecified"))
      (node (ref "R6") (pin "1") (pinfunction "1_1") (pintype "input"))
    )
    (net (code "73") (name "Net-(LED2-A)") (class "Default")
      (node (ref "LED2") (pin "2") (pinfunction "A_2") (pintype "unspecified"))
      (node (ref "R8") (pin "1") (pinfunction "1_1") (pintype "input"))
    )
    (net (code "74") (name "Net-(LED3-A)") (class "Default")
      (node (ref "LED3") (pin "2") (pinfunction "A_2") (pintype "unspecified"))
      (node (ref "R7") (pin "1") (pinfunction "1_1") (pintype "input"))
    )
    (net (code "75") (name "Net-(LED4-K)") (class "Default")
      (node (ref "LED4") (pin "1") (pinfunction "K_1") (pintype "unspecified"))
      (node (ref "R2") (pin "2") (pinfunction "2_2") (pintype "input"))
    )
    (net (code "76") (name "Net-(LED5-A)") (class "Default")
      (node (ref "LED5") (pin "2") (pinfunction "A_2") (pintype "unspecified"))
      (node (ref "R3") (pin "1") (pinfunction "1_1") (pintype "input"))
    )
    (net (code "77") (name "Net-(Q1-B)") (class "Default")
      (node (ref "Q1") (pin "1") (pinfunction "B_1") (pintype "input"))
      (node (ref "R10") (pin "2") (pinfunction "2_2") (pintype "input"))
      (node (ref "R9") (pin "1") (pinfunction "1_1") (pintype "input"))
    )
    (net (code "78") (name "Net-(总电源-A)") (class "Default")
      (node (ref "R1") (pin "1") (pinfunction "1_1") (pintype "input"))
      (node (ref "总电源") (pin "2") (pinfunction "A_2") (pintype "unspecified"))
    )
    (net (code "79") (name "unconnected-(ESP8266-Pad3)") (class "Default")
      (node (ref "ESP8266") (pin "3") (pinfunction "3_3") (pintype "input+no_connect"))
    )
    (net (code "80") (name "unconnected-(ESP8266-Pad4)") (class "Default")
      (node (ref "ESP8266") (pin "4") (pinfunction "4_4") (pintype "input+no_connect"))
    )
    (net (code "81") (name "unconnected-(ESP8266-Pad5)") (class "Default")
      (node (ref "ESP8266") (pin "5") (pinfunction "5_5") (pintype "input+no_connect"))
    )
    (net (code "82") (name "unconnected-(H2-Pad1)") (class "Default")
      (node (ref "H2") (pin "1") (pinfunction "1_1") (pintype "unspecified"))
    )
    (net (code "83") (name "unconnected-(H2-Pad2)") (class "Default")
      (node (ref "H2") (pin "2") (pinfunction "2_2") (pintype "unspecified"))
    )
    (net (code "84") (name "unconnected-(H2-Pad3)") (class "Default")
      (node (ref "H2") (pin "3") (pinfunction "3_3") (pintype "unspecified"))
    )
    (net (code "85") (name "unconnected-(H2-Pad4)") (class "Default")
      (node (ref "H2") (pin "4") (pinfunction "4_4") (pintype "unspecified"))
    )
    (net (code "86") (name "unconnected-(H2-Pad5)") (class "Default")
      (node (ref "H2") (pin "5") (pinfunction "5_5") (pintype "unspecified"))
    )
    (net (code "87") (name "unconnected-(H2-Pad6)") (class "Default")
      (node (ref "H2") (pin "6") (pinfunction "6_6") (pintype "unspecified"))
    )
    (net (code "88") (name "unconnected-(H2-Pad7)") (class "Default")
      (node (ref "H2") (pin "7") (pinfunction "7_7") (pintype "unspecified"))
    )
    (net (code "89") (name "unconnected-(H2-Pad8)") (class "Default")
      (node (ref "H2") (pin "8") (pinfunction "8_8") (pintype "unspecified"))
    )
    (net (code "90") (name "unconnected-(H3-Pad1)") (class "Default")
      (node (ref "H3") (pin "1") (pinfunction "1_1") (pintype "unspecified"))
    )
    (net (code "91") (name "unconnected-(H3-Pad2)") (class "Default")
      (node (ref "H3") (pin "2") (pinfunction "2_2") (pintype "unspecified"))
    )
    (net (code "92") (name "unconnected-(H3-Pad3)") (class "Default")
      (node (ref "H3") (pin "3") (pinfunction "3_3") (pintype "unspecified"))
    )
    (net (code "93") (name "unconnected-(H3-Pad4)") (class "Default")
      (node (ref "H3") (pin "4") (pinfunction "4_4") (pintype "unspecified"))
    )
    (net (code "94") (name "unconnected-(H3-Pad5)") (class "Default")
      (node (ref "H3") (pin "5") (pinfunction "5_5") (pintype "unspecified"))
    )
    (net (code "95") (name "unconnected-(H3-Pad6)") (class "Default")
      (node (ref "H3") (pin "6") (pinfunction "6_6") (pintype "unspecified"))
    )
    (net (code "96") (name "unconnected-(H3-Pad7)") (class "Default")
      (node (ref "H3") (pin "7") (pinfunction "7_7") (pintype "unspecified"))
    )
    (net (code "97") (name "unconnected-(H3-Pad8)") (class "Default")
      (node (ref "H3") (pin "8") (pinfunction "8_8") (pintype "unspecified"))
    )
    (net (code "98") (name "unconnected-(U1-+3V3-Pad78)") (class "Default")
      (node (ref "U1") (pin "78") (pinfunction "+3V3_78") (pintype "unspecified"))
    )
    (net (code "99") (name "unconnected-(U1-+5V0-Pad40)") (class "Default")
      (node (ref "U1") (pin "40") (pinfunction "+5V0_40") (pintype "unspecified"))
    )
    (net (code "100") (name "unconnected-(U1-+5V0-Pad80)") (class "Default")
      (node (ref "U1") (pin "80") (pinfunction "+5V0_80") (pintype "unspecified"))
    )
    (net (code "101") (name "unconnected-(U1-AGND-Pad37)") (class "Default")
      (node (ref "U1") (pin "37") (pinfunction "AGND_37") (pintype "unspecified"))
    )
    (net (code "102") (name "unconnected-(U1-EXT-BAT+-Pad66)") (class "Default")
      (node (ref "U1") (pin "66") (pinfunction "EXT-BAT+_66") (pintype "unspecified"))
    )
    (net (code "103") (name "unconnected-(U1-EXT_REF+-Pad2)") (class "Default")
      (node (ref "U1") (pin "2") (pinfunction "EXT_REF+_2") (pintype "unspecified"))
    )
    (net (code "104") (name "unconnected-(U1-GND-Pad77)") (class "Default")
      (node (ref "U1") (pin "77") (pinfunction "GND_77") (pintype "unspecified"))
    )
    (net (code "105") (name "unconnected-(U1-GND-Pad79)") (class "Default")
      (node (ref "U1") (pin "79") (pinfunction "GND_79") (pintype "unspecified"))
    )
    (net (code "106") (name "unconnected-(U1-PB0-Pad11)") (class "Default")
      (node (ref "U1") (pin "11") (pinfunction "PB0_11") (pintype "unspecified"))
    )
    (net (code "107") (name "unconnected-(U1-PB12-Pad26)") (class "Default")
      (node (ref "U1") (pin "26") (pinfunction "PB12_26") (pintype "unspecified"))
    )
    (net (code "108") (name "unconnected-(U1-PB13-Pad25)") (class "Default")
      (node (ref "U1") (pin "25") (pinfunction "PB13_25") (pintype "unspecified"))
    )
    (net (code "109") (name "unconnected-(U1-PB14-Pad28)") (class "Default")
      (node (ref "U1") (pin "28") (pinfunction "PB14_28") (pintype "unspecified"))
    )
    (net (code "110") (name "unconnected-(U1-PB15-Pad27)") (class "Default")
      (node (ref "U1") (pin "27") (pinfunction "PB15_27") (pintype "unspecified"))
    )
    (net (code "111") (name "unconnected-(U1-PC0-Pad54)") (class "Default")
      (node (ref "U1") (pin "54") (pinfunction "PC0_54") (pintype "unspecified"))
    )
    (net (code "112") (name "unconnected-(U1-PC1-Pad55)") (class "Default")
      (node (ref "U1") (pin "55") (pinfunction "PC1_55") (pintype "unspecified"))
    )
    (net (code "113") (name "unconnected-(U1-PC2-Pad56)") (class "Default")
      (node (ref "U1") (pin "56") (pinfunction "PC2_56") (pintype "unspecified"))
    )
    (net (code "114") (name "unconnected-(U1-PC3-Pad57)") (class "Default")
      (node (ref "U1") (pin "57") (pinfunction "PC3_57") (pintype "unspecified"))
    )
    (net (code "115") (name "unconnected-(U1-PC4-Pad9)") (class "Default")
      (node (ref "U1") (pin "9") (pinfunction "PC4_9") (pintype "unspecified"))
    )
    (net (code "116") (name "unconnected-(U1-PC8-Pad43)") (class "Default")
      (node (ref "U1") (pin "43") (pinfunction "PC8_43") (pintype "unspecified"))
    )
    (net (code "117") (name "unconnected-(U1-PC13-Pad48)") (class "Default")
      (node (ref "U1") (pin "48") (pinfunction "PC13_48") (pintype "unspecified"))
    )
    (net (code "118") (name "unconnected-(U1-PD3-Pad41)") (class "Default")
      (node (ref "U1") (pin "41") (pinfunction "PD3_41") (pintype "unspecified"))
    )
    (net (code "119") (name "unconnected-(U1-PE1-Pad58)") (class "Default")
      (node (ref "U1") (pin "58") (pinfunction "PE1_58") (pintype "unspecified"))
    )
    (net (code "120") (name "unconnected-(U1-PE2-Pad53)") (class "Default")
      (node (ref "U1") (pin "53") (pinfunction "PE2_53") (pintype "unspecified"))
    )
    (net (code "121") (name "unconnected-(U1-PE3-Pad52)") (class "Default")
      (node (ref "U1") (pin "52") (pinfunction "PE3_52") (pintype "unspecified"))
    )
    (net (code "122") (name "unconnected-(U1-PE4-Pad51)") (class "Default")
      (node (ref "U1") (pin "51") (pinfunction "PE4_51") (pintype "unspecified"))
    )
    (net (code "123") (name "unconnected-(U1-PE5-Pad50)") (class "Default")
      (node (ref "U1") (pin "50") (pinfunction "PE5_50") (pintype "unspecified"))
    )
    (net (code "124") (name "unconnected-(U1-PE6-Pad49)") (class "Default")
      (node (ref "U1") (pin "49") (pinfunction "PE6_49") (pintype "unspecified"))
    )
    (net (code "125") (name "unconnected-(U1-PE7-Pad13)") (class "Default")
      (node (ref "U1") (pin "13") (pinfunction "PE7_13") (pintype "unspecified"))
    )
    (net (code "126") (name "unconnected-(U1-PE9-Pad15)") (class "Default")
      (node (ref "U1") (pin "15") (pinfunction "PE9_15") (pintype "unspecified"))
    )
    (net (code "127") (name "unconnected-(U1-PE11-Pad17)") (class "Default")
      (node (ref "U1") (pin "17") (pinfunction "PE11_17") (pintype "unspecified"))
    )
    (net (code "128") (name "unconnected-(U1-PE12-Pad20)") (class "Default")
      (node (ref "U1") (pin "20") (pinfunction "PE12_20") (pintype "unspecified"))
    )
    (net (code "129") (name "unconnected-(U1-PE13-Pad19)") (class "Default")
      (node (ref "U1") (pin "19") (pinfunction "PE13_19") (pintype "unspecified"))
    )
    (net (code "130") (name "unconnected-(U1-PE14-Pad22)") (class "Default")
      (node (ref "U1") (pin "22") (pinfunction "PE14_22") (pintype "unspecified"))
    )
    (net (code "131") (name "unconnected-(U1-PE15-Pad21)") (class "Default")
      (node (ref "U1") (pin "21") (pinfunction "PE15_21") (pintype "unspecified"))
    )
    (net (code "132") (name "unconnected-(U2-Pad1)") (class "Default")
      (node (ref "U2") (pin "1") (pinfunction "1_1") (pintype "unspecified"))
    )
    (net (code "133") (name "unconnected-(U2-Pad4)") (class "Default")
      (node (ref "U2") (pin "4") (pinfunction "4_4") (pintype "unspecified"))
    )
    (net (code "134") (name "unconnected-(U3-Pad1)") (class "Default")
      (node (ref "U3") (pin "1") (pinfunction "1_1") (pintype "unspecified"))
    )
    (net (code "135") (name "unconnected-(U3-Pad4)") (class "Default")
      (node (ref "U3") (pin "4") (pinfunction "4_4") (pintype "unspecified"))
    )
  )
)
